# CHECK_AMPERE.net
KiCad netlist of a schematic drawn in Altium Designer
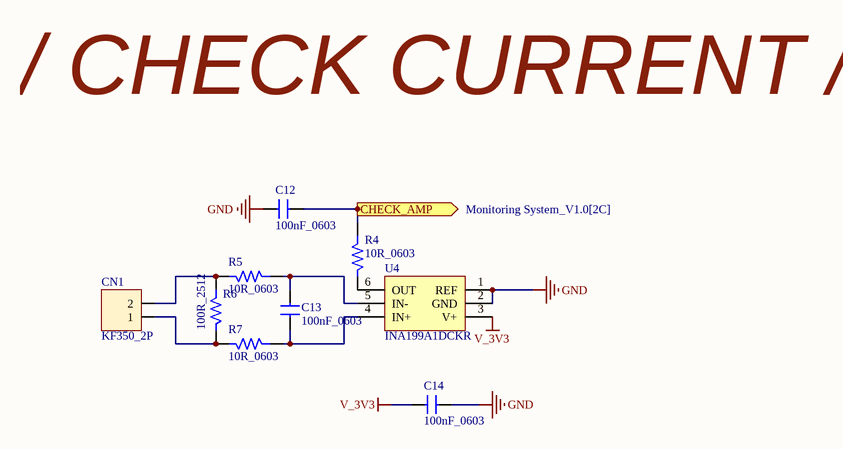
[diagram p0: CHECK_AMPERE.SchDoc]

(export (version "E")
  (design (tool "Eeschema 10.0.6"))
  (components
    (comp (ref "C12")
      (value "100nF_0603")
      (footprint "CN-SMD-0603")
      (description "Cap SMD, 0.06x0.03 inch, 1.55x0.85 mm - 1608")
      (libsource (lib "LYAM_LIB") (part "CAP 0603 104"))
    )
    (comp (ref "C13")
      (value "100nF_0603")
      (footprint "CN-SMD-0603")
      (description "Cap SMD, 0.06x0.03 inch, 1.55x0.85 mm - 1608")
      (libsource (lib "LYAM_LIB") (part "CAP 0603 104"))
    )
    (comp (ref "C14")
      (value "100nF_0603")
      (footprint "CN-SMD-0603")
      (description "Cap SMD, 0.06x0.03 inch, 1.55x0.85 mm - 1608")
      (libsource (lib "LYAM_LIB") (part "CAP 0603 104"))
    )
    (comp (ref "CN1")
      (value "KF350_2P")
      (footprint "KF350-2P")
      (description "Terminal Block 3.5mm")
      (libsource (lib "LYAM_LIB") (part "KF350_2P"))
    )
    (comp (ref "R4")
      (value "10R_0603")
      (footprint "RES-SMD-0603")
      (description "Resistor SMD, 0.06x0.03 inch, 1.55x0.85 mm - 1608, 1/10W")
      (libsource (lib "LYAM_LIB") (part "RES 0603 10R"))
    )
    (comp (ref "R5")
      (value "10R_0603")
      (footprint "RES-SMD-0603")
      (description "Resistor SMD, 0.06x0.03 inch, 1.55x0.85 mm - 1608, 1/10W")
      (libsource (lib "LYAM_LIB") (part "RES 0603 10R"))
    )
    (comp (ref "R6")
      (value "100R_2512")
      (footprint "RES-SMD-2512")
      (description "Resistor SMD, 0.25x0.12 inch, 6.3x3.2 mm - 6332, 1W")
      (libsource (lib "LYAM_LIB") (part "RES 2512 100R"))
    )
    (comp (ref "R7")
      (value "10R_0603")
      (footprint "RES-SMD-0603")
      (description "Resistor SMD, 0.06x0.03 inch, 1.55x0.85 mm - 1608, 1/10W")
      (libsource (lib "LYAM_LIB") (part "RES 0603 10R"))
    )
    (comp (ref "U4")
      (value "INA199A1DCKR")
      (footprint "SC70-6")
      (libsource (lib "LYAM_LIB") (part "INA199A1DCKR"))
    )
  )
  (nets
    (net (code "1") (name "/CHECK_AMP") (class "Default")
      (node (ref "C12") (pin "1") (pinfunction "1_1") (pintype "passive"))
      (node (ref "R4") (pin "2") (pinfunction "2_2") (pintype "passive"))
    )
    (net (code "2") (name "GND") (class "Default")
      (node (ref "C12") (pin "2") (pinfunction "2_2") (pintype "passive"))
      (node (ref "C14") (pin "1") (pinfunction "1_1") (pintype "passive"))
      (node (ref "U4") (pin "1") (pinfunction "REF_1") (pintype "passive"))
      (node (ref "U4") (pin "2") (pinfunction "GND_2") (pintype "passive"))
    )
    (net (code "3") (name "Net-(CN1-Pad1)") (class "Default")
      (node (ref "CN1") (pin "1") (pinfunction "1_1") (pintype "passive"))
      (node (ref "R6") (pin "1") (pinfunction "1_1") (pintype "passive"))
      (node (ref "R7") (pin "1") (pinfunction "1_1") (pintype "passive"))
    )
    (net (code "4") (name "Net-(CN1-Pad2)") (class "Default")
      (node (ref "CN1") (pin "2") (pinfunction "2_2") (pintype "passive"))
      (node (ref "R5") (pin "1") (pinfunction "1_1") (pintype "passive"))
      (node (ref "R6") (pin "2") (pinfunction "2_2") (pintype "passive"))
    )
    (net (code "5") (name "Net-(U4-IN+)") (class "Default")
      (node (ref "C13") (pin "1") (pinfunction "1_1") (pintype "passive"))
      (node (ref "R7") (pin "2") (pinfunction "2_2") (pintype "passive"))
      (node (ref "U4") (pin "4") (pinfunction "IN+_4") (pintype "passive"))
    )
    (net (code "6") (name "Net-(U4-IN-)") (class "Default")
      (node (ref "C13") (pin "2") (pinfunction "2_2") (pintype "passive"))
      (node (ref "R5") (pin "2") (pinfunction "2_2") (pintype "passive"))
      (node (ref "U4") (pin "5") (pinfunction "IN-_5") (pintype "passive"))
    )
    (net (code "7") (name "Net-(U4-OUT)") (class "Default")
      (node (ref "R4") (pin "1") (pinfunction "1_1") (pintype "passive"))
      (node (ref "U4") (pin "6") (pinfunction "OUT_6") (pintype "passive"))
    )
    (net (code "8") (name "V_3V3") (class "Default")
      (node (ref "C14") (pin "2") (pinfunction "2_2") (pintype "passive"))
      (node (ref "U4") (pin "3") (pinfunction "V+_3") (pintype "passive"))
    )
  )
)
